# P-MT3620RDB-1-6_FTDI.net
KiCad netlist of a schematic drawn in Altium Designer
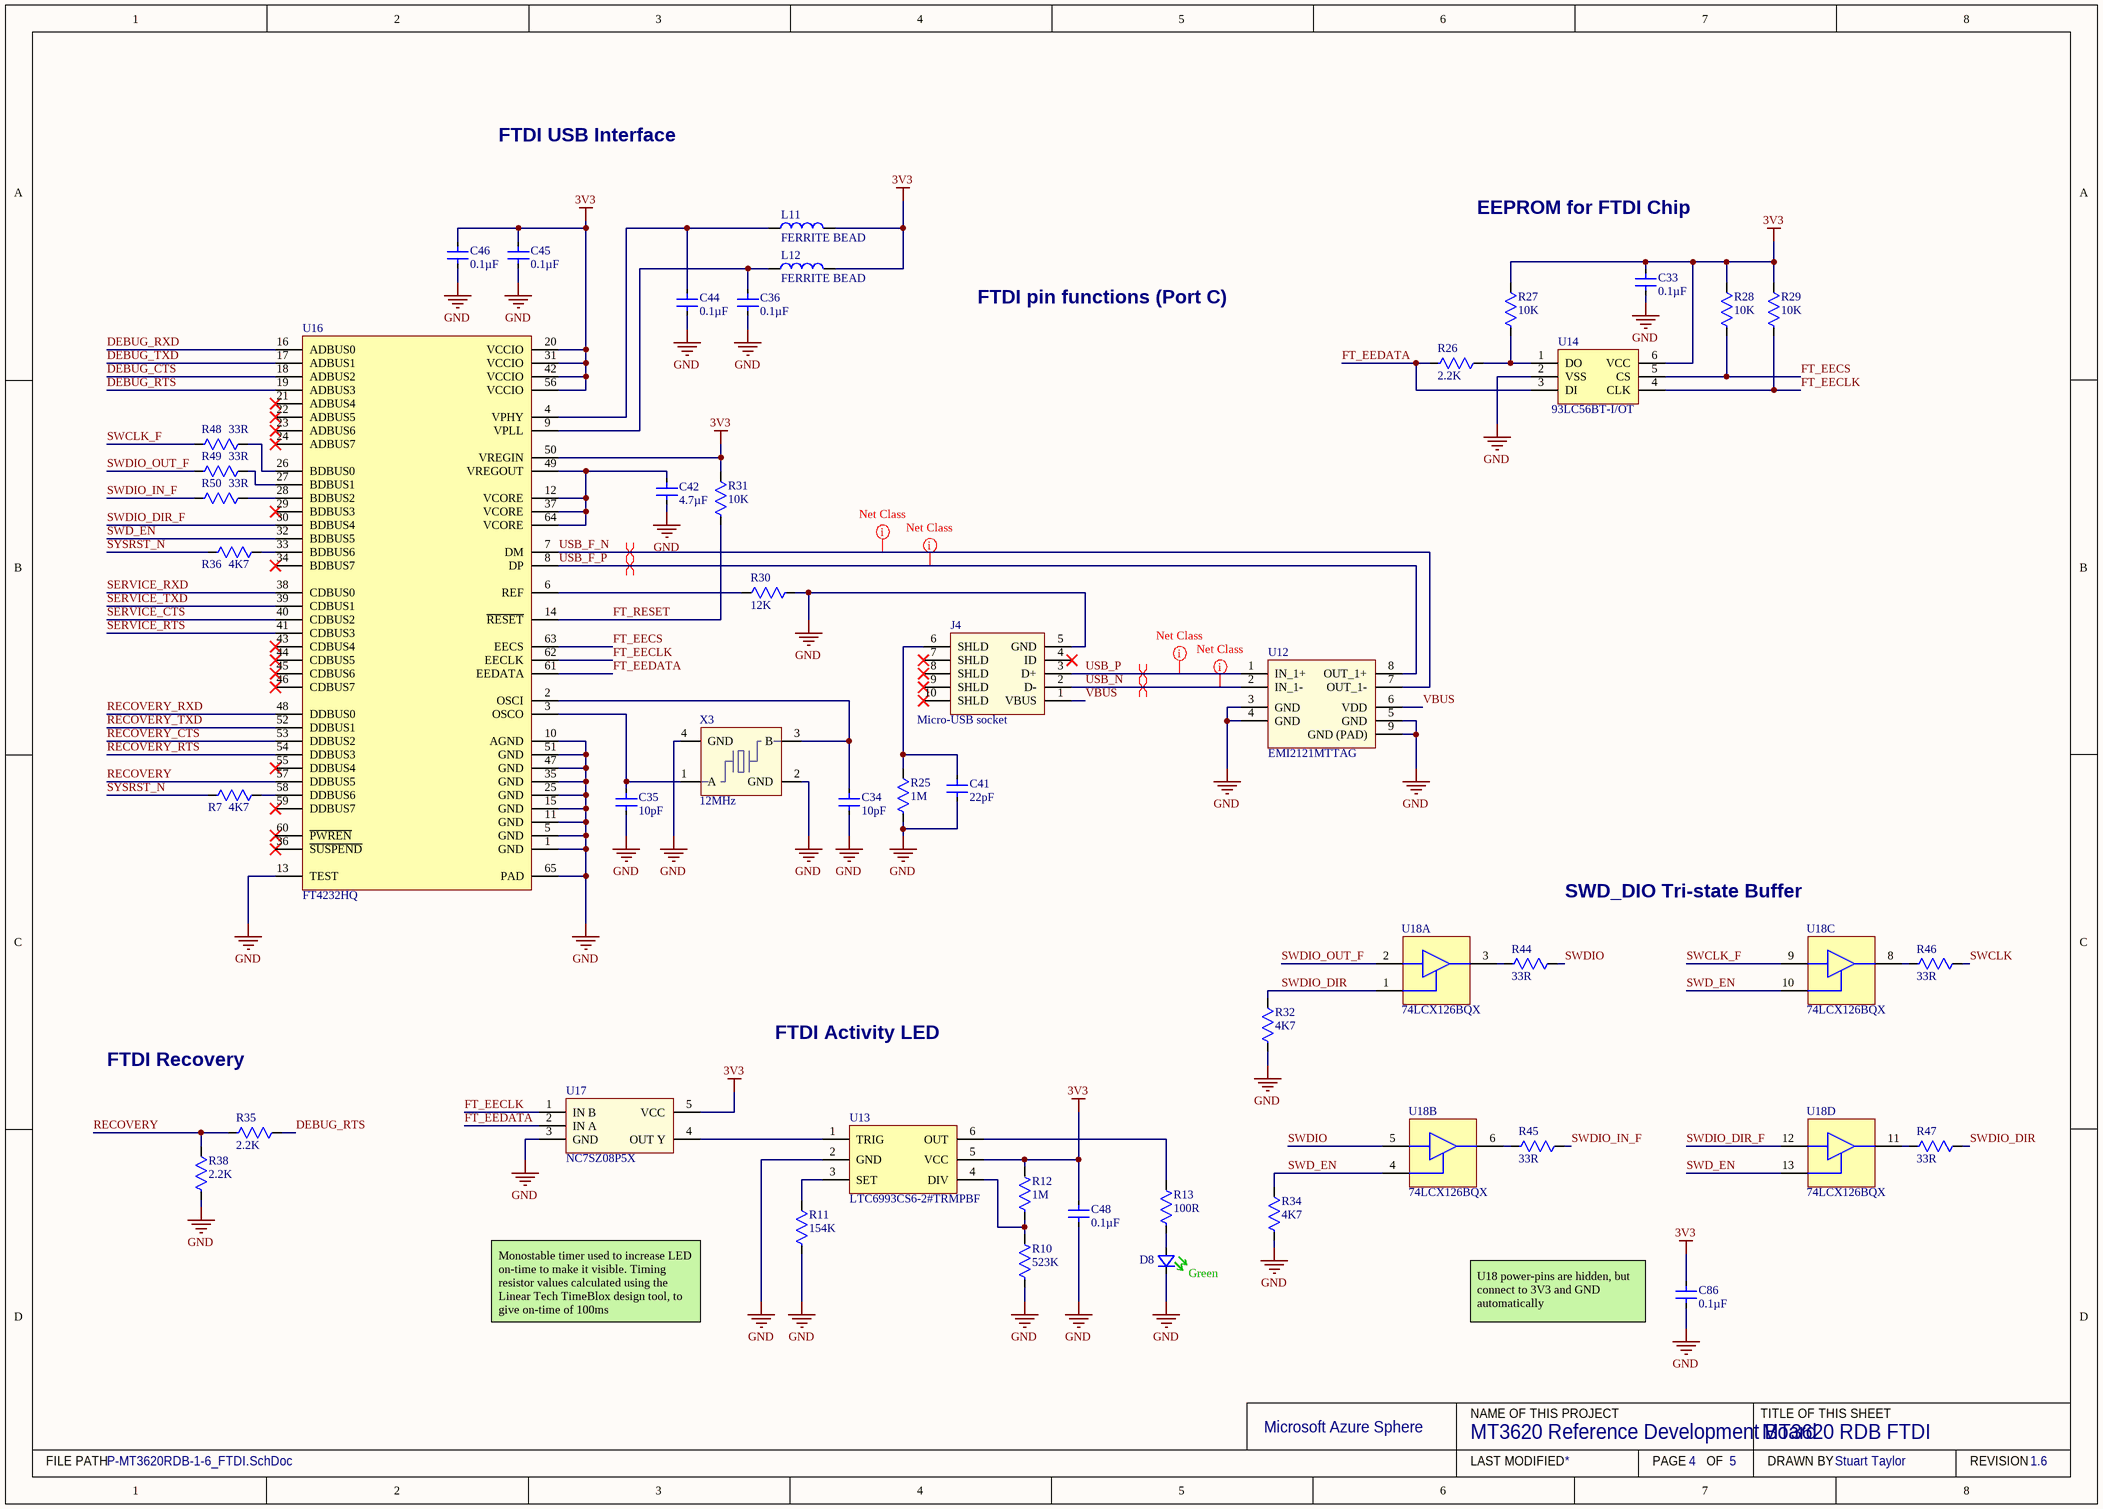
[diagram p0: P-MT3620RDB-1-6_FTDI.SchDoc]

(export (version "E")
  (design (tool "Eeschema 10.0.6"))
  (components
    (comp (ref "C33")
      (value "0.1µF")
      (footprint "CAPC1005-EIA0402 0.55MM MED")
      (description "CAP CER 0.1UF 50V 10% X7R 0402")
      (fields
        (field (name "MANUFACTURER") "TDK Corporation")
        (field (name "MANUFACTURER PART NUMBER") "C1005X7R1H104K050BB")
        (field (name "CAPACITANCE") "0.1µF")
      )
      (libsource (lib "TDK_Capacitor_C_0402") (part "0.1µF 0402 X7R 50V"))
    )
    (comp (ref "C34")
      (value "10pF")
      (footprint "CAPC1005-EIA0402 0.55MM MED")
      (description "CAP CER 10PF 50V NP0 0402")
      (fields
        (field (name "MANUFACTURER") "TDK Corporation")
        (field (name "MANUFACTURER PART NUMBER") "C1005C0G1H100D050BA")
        (field (name "CAPACITANCE") "10pF")
      )
      (libsource (lib "TDK_Capacitor_C_0402") (part "10pF 0402 C0G, NP0 50V"))
    )
    (comp (ref "C35")
      (value "10pF")
      (footprint "CAPC1005-EIA0402 0.55MM MED")
      (description "CAP CER 10PF 50V NP0 0402")
      (fields
        (field (name "MANUFACTURER") "TDK Corporation")
        (field (name "MANUFACTURER PART NUMBER") "C1005C0G1H100D050BA")
        (field (name "CAPACITANCE") "10pF")
      )
      (libsource (lib "TDK_Capacitor_C_0402") (part "10pF 0402 C0G, NP0 50V"))
    )
    (comp (ref "C36")
      (value "0.1µF")
      (footprint "CAPC1005-EIA0402 0.55MM MED")
      (description "CAP CER 0.1UF 50V 10% X7R 0402")
      (fields
        (field (name "MANUFACTURER") "TDK Corporation")
        (field (name "MANUFACTURER PART NUMBER") "C1005X7R1H104K050BB")
        (field (name "CAPACITANCE") "0.1µF")
      )
      (libsource (lib "TDK_Capacitor_C_0402") (part "0.1µF 0402 X7R 50V"))
    )
    (comp (ref "C41")
      (value "22pF")
      (footprint "CAPC1005-EIA0402 0.55MM MED")
      (description "CAP CER 22PF 50V 5% NP0 0402")
      (fields
        (field (name "MANUFACTURER") "TDK Corporation")
        (field (name "MANUFACTURER PART NUMBER") "C1005C0G1H220J050BA")
        (field (name "CAPACITANCE") "22pF")
      )
      (libsource (lib "TDK_Capacitor_C_0402") (part "22pF 0402 C0G, NP0 50V"))
    )
    (comp (ref "C42")
      (value "4.7µF")
      (footprint "CAPC1005-EIA0402 0.55MM MED")
      (description "CAP CER 4.7UF 10V 10% X5R 0402")
      (fields
        (field (name "MANUFACTURER") "TDK Corporation")
        (field (name "MANUFACTURER PART NUMBER") "C1005X5R1A475K050BC")
        (field (name "CAPACITANCE") "4.7µF")
      )
      (libsource (lib "TDK_Capacitor_C_0402") (part "4.7µF 0402 X5R 10V"))
    )
    (comp (ref "C44")
      (value "0.1µF")
      (footprint "CAPC1005-EIA0402 0.55MM MED")
      (description "CAP CER 0.1UF 50V 10% X7R 0402")
      (fields
        (field (name "MANUFACTURER") "TDK Corporation")
        (field (name "MANUFACTURER PART NUMBER") "C1005X7R1H104K050BB")
        (field (name "CAPACITANCE") "0.1µF")
      )
      (libsource (lib "TDK_Capacitor_C_0402") (part "0.1µF 0402 X7R 50V"))
    )
    (comp (ref "C45")
      (value "0.1µF")
      (footprint "CAPC1005-EIA0402 0.55MM MED")
      (description "CAP CER 0.1UF 50V 10% X7R 0402")
      (fields
        (field (name "MANUFACTURER") "TDK Corporation")
        (field (name "MANUFACTURER PART NUMBER") "C1005X7R1H104K050BB")
        (field (name "CAPACITANCE") "0.1µF")
      )
      (libsource (lib "TDK_Capacitor_C_0402") (part "0.1µF 0402 X7R 50V"))
    )
    (comp (ref "C46")
      (value "0.1µF")
      (footprint "CAPC1005-EIA0402 0.55MM MED")
      (description "CAP CER 0.1UF 50V 10% X7R 0402")
      (fields
        (field (name "MANUFACTURER") "TDK Corporation")
        (field (name "MANUFACTURER PART NUMBER") "C1005X7R1H104K050BB")
        (field (name "CAPACITANCE") "0.1µF")
      )
      (libsource (lib "TDK_Capacitor_C_0402") (part "0.1µF 0402 X7R 50V"))
    )
    (comp (ref "C48")
      (value "0.1µF")
      (footprint "CAPC1005-EIA0402 0.55MM MED")
      (description "CAP CER 0.1UF 50V 10% X7R 0402")
      (fields
        (field (name "MANUFACTURER") "TDK Corporation")
        (field (name "MANUFACTURER PART NUMBER") "C1005X7R1H104K050BB")
        (field (name "CAPACITANCE") "0.1µF")
      )
      (libsource (lib "TDK_Capacitor_C_0402") (part "0.1µF 0402 X7R 50V"))
    )
    (comp (ref "C86")
      (value "0.1µF")
      (footprint "CAPC1005-EIA0402 0.55MM MED")
      (description "CAP CER 0.1UF 50V 10% X7R 0402")
      (fields
        (field (name "MANUFACTURER") "TDK Corporation")
        (field (name "MANUFACTURER PART NUMBER") "C1005X7R1H104K050BB")
        (field (name "CAPACITANCE") "0.1µF")
      )
      (libsource (lib "TDK_Capacitor_C_0402") (part "0.1µF 0402 X7R 50V"))
    )
    (comp (ref "D8")
      (value "Green LED")
      (footprint "Rohm SML-D12 Green")
      (description "1.6 x 0.8 x 0.55mm (0603) LED 560nm Green")
      (fields
        (field (name "MANUFACTURER") "Rohm Semiconductor")
        (field (name "MANUFACTURER PART NUMBER") "SML-D12P8WT86")
        (field (name "COLOUR") "Green")
      )
      (libsource (lib "Rohm") (part "SML-D12P"))
    )
    (comp (ref "J4")
      (value "Micro-USB socket")
      (footprint "MCR-B-S-RA-SMT-CS5-T/R")
      (fields
        (field (name "MANUFACTURER") "Adam Tech")
        (field (name "MANUFACTURERS PART NUMBER") "MCR-B-S-RA-SMT-CS5-T/R")
      )
      (libsource (lib "AdamTech") (part "MCR-B-S-RA-SMT-CS5-T/R"))
    )
    (comp (ref "L11")
      (value "FERRITE BEAD")
      (footprint "CAPC1005-EIA0402 0.55MM MED")
      (description "FERRITE BEAD 120 OHM 0402 1LN")
      (fields
        (field (name "MANUFACTURER") "Murata Electronics North America")
        (field (name "MANUFACTURER PART NUMBER") "BLM15PD121SN1D")
      )
      (libsource (lib "Murata") (part "BLM15PD121SN1D"))
    )
    (comp (ref "L12")
      (value "FERRITE BEAD")
      (footprint "CAPC1005-EIA0402 0.55MM MED")
      (description "FERRITE BEAD 120 OHM 0402 1LN")
      (fields
        (field (name "MANUFACTURER") "Murata Electronics North America")
        (field (name "MANUFACTURER PART NUMBER") "BLM15PD121SN1D")
      )
      (libsource (lib "Murata") (part "BLM15PD121SN1D"))
    )
    (comp (ref "R7")
      (value "4K7")
      (footprint "RES 0402 MEDIUM DENSITY")
      (description "RES 4.7K OHM 1/10W 1% 0402 SMD")
      (fields
        (field (name "MANUFACTURER") "Panasonic Electronic Components")
        (field (name "MANUFACTURER PART NUMBER") "ERJ-2RKF4701X")
        (field (name "RESISTANCE (OHMS)") "4K7")
      )
      (libsource (lib "Panasonic_Resistor_ERJ2R") (part "4.7K"))
    )
    (comp (ref "R10")
      (value "523K")
      (footprint "RES 0402 MEDIUM DENSITY")
      (description "RES 523K OHM 1/10W 1% 0402 SMD")
      (fields
        (field (name "MANUFACTURER") "Panasonic Electronic Components")
        (field (name "MANUFACTURER PART NUMBER") "ERJ-2RKF5233X")
        (field (name "RESISTANCE (OHMS)") "523K")
      )
      (libsource (lib "Panasonic_Resistor_ERJ2R") (part "523K"))
    )
    (comp (ref "R11")
      (value "154K")
      (footprint "RES 0402 MEDIUM DENSITY")
      (description "RES 154K OHM 1/10W 1% 0402 SMD")
      (fields
        (field (name "MANUFACTURER") "Panasonic Electronic Components")
        (field (name "MANUFACTURER PART NUMBER") "ERJ-2RKF1543X")
        (field (name "RESISTANCE (OHMS)") "154K")
      )
      (libsource (lib "Panasonic_Resistor_ERJ2R") (part "154K"))
    )
    (comp (ref "R12")
      (value "1M")
      (footprint "RES 0402 MEDIUM DENSITY")
      (description "RES 1M OHM 1/10W 1% 0402 SMD")
      (fields
        (field (name "MANUFACTURER") "Panasonic Electronic Components")
        (field (name "MANUFACTURER PART NUMBER") "ERJ-2RKF1004X")
        (field (name "RESISTANCE (OHMS)") "1M")
      )
      (libsource (lib "Panasonic_Resistor_ERJ2R") (part "1M"))
    )
    (comp (ref "R13")
      (value "100R")
      (footprint "RES 0402 MEDIUM DENSITY")
      (description "RES 100 OHM 1/10W 1% 0402 SMD")
      (fields
        (field (name "MANUFACTURER") "Panasonic Electronic Components")
        (field (name "MANUFACTURER PART NUMBER") "ERJ-2RKF1000X")
        (field (name "RESISTANCE (OHMS)") "100R")
      )
      (libsource (lib "Panasonic_Resistor_ERJ2R") (part "100R"))
    )
    (comp (ref "R25")
      (value "1M")
      (footprint "RES 0402 MEDIUM DENSITY")
      (description "RES 1M OHM 1/10W 1% 0402 SMD")
      (fields
        (field (name "MANUFACTURER") "Panasonic Electronic Components")
        (field (name "MANUFACTURER PART NUMBER") "ERJ-2RKF1004X")
        (field (name "RESISTANCE (OHMS)") "1M")
      )
      (libsource (lib "Panasonic_Resistor_ERJ2R") (part "1M"))
    )
    (comp (ref "R26")
      (value "2.2K")
      (footprint "RES 0402 MEDIUM DENSITY")
      (description "RES 2.2K OHM 1/10W 1% 0402 SMD")
      (fields
        (field (name "MANUFACTURER") "Panasonic Electronic Components")
        (field (name "MANUFACTURER PART NUMBER") "ERJ-2RKF2201X")
        (field (name "RESISTANCE (OHMS)") "2.2K")
      )
      (libsource (lib "Panasonic_Resistor_ERJ2R") (part "2.2K"))
    )
    (comp (ref "R27")
      (value "10K")
      (footprint "RES 0402 MEDIUM DENSITY")
      (description "RES 10K OHM 1/10W 1% 0402 SMD")
      (fields
        (field (name "MANUFACTURER") "Panasonic Electronic Components")
        (field (name "MANUFACTURER PART NUMBER") "ERJ-2RKF1002X")
        (field (name "RESISTANCE (OHMS)") "10K")
      )
      (libsource (lib "Panasonic_Resistor_ERJ2R") (part "10K"))
    )
    (comp (ref "R28")
      (value "10K")
      (footprint "RES 0402 MEDIUM DENSITY")
      (description "RES 10K OHM 1/10W 1% 0402 SMD")
      (fields
        (field (name "MANUFACTURER") "Panasonic Electronic Components")
        (field (name "MANUFACTURER PART NUMBER") "ERJ-2RKF1002X")
        (field (name "RESISTANCE (OHMS)") "10K")
      )
      (libsource (lib "Panasonic_Resistor_ERJ2R") (part "10K"))
    )
    (comp (ref "R29")
      (value "10K")
      (footprint "RES 0402 MEDIUM DENSITY")
      (description "RES 10K OHM 1/10W 1% 0402 SMD")
      (fields
        (field (name "MANUFACTURER") "Panasonic Electronic Components")
        (field (name "MANUFACTURER PART NUMBER") "ERJ-2RKF1002X")
        (field (name "RESISTANCE (OHMS)") "10K")
      )
      (libsource (lib "Panasonic_Resistor_ERJ2R") (part "10K"))
    )
    (comp (ref "R30")
      (value "12K")
      (footprint "RES 0402 MEDIUM DENSITY")
      (description "RES 12K OHM 1/10W 1% 0402 SMD")
      (fields
        (field (name "MANUFACTURER") "Panasonic Electronic Components")
        (field (name "MANUFACTURER PART NUMBER") "ERJ-2RKF1202X")
        (field (name "RESISTANCE (OHMS)") "12K")
      )
      (libsource (lib "Panasonic_Resistor_ERJ2R") (part "12K"))
    )
    (comp (ref "R31")
      (value "10K")
      (footprint "RES 0402 MEDIUM DENSITY")
      (description "RES 10K OHM 1/10W 1% 0402 SMD")
      (fields
        (field (name "MANUFACTURER") "Panasonic Electronic Components")
        (field (name "MANUFACTURER PART NUMBER") "ERJ-2RKF1002X")
        (field (name "RESISTANCE (OHMS)") "10K")
      )
      (libsource (lib "Panasonic_Resistor_ERJ2R") (part "10K"))
    )
    (comp (ref "R32")
      (value "4K7")
      (footprint "RES 0402 MEDIUM DENSITY")
      (description "RES 4.7K OHM 1/10W 1% 0402 SMD")
      (fields
        (field (name "MANUFACTURER") "Panasonic Electronic Components")
        (field (name "MANUFACTURER PART NUMBER") "ERJ-2RKF4701X")
        (field (name "RESISTANCE (OHMS)") "4K7")
      )
      (libsource (lib "Panasonic_Resistor_ERJ2R") (part "4.7K"))
    )
    (comp (ref "R34")
      (value "4K7")
      (footprint "RES 0402 MEDIUM DENSITY")
      (description "RES 4.7K OHM 1/10W 1% 0402 SMD")
      (fields
        (field (name "MANUFACTURER") "Panasonic Electronic Components")
        (field (name "MANUFACTURER PART NUMBER") "ERJ-2RKF4701X")
        (field (name "RESISTANCE (OHMS)") "4K7")
      )
      (libsource (lib "Panasonic_Resistor_ERJ2R") (part "4.7K"))
    )
    (comp (ref "R35")
      (value "2.2K")
      (footprint "RES 0402 MEDIUM DENSITY")
      (description "RES 2.2K OHM 1/10W 1% 0402 SMD")
      (fields
        (field (name "MANUFACTURER") "Panasonic Electronic Components")
        (field (name "MANUFACTURER PART NUMBER") "ERJ-2RKF2201X")
        (field (name "RESISTANCE (OHMS)") "2.2K")
      )
      (libsource (lib "Panasonic_Resistor_ERJ2R") (part "2.2K"))
    )
    (comp (ref "R36")
      (value "4K7")
      (footprint "RES 0402 MEDIUM DENSITY")
      (description "RES 4.7K OHM 1/10W 1% 0402 SMD")
      (fields
        (field (name "MANUFACTURER") "Panasonic Electronic Components")
        (field (name "MANUFACTURER PART NUMBER") "ERJ-2RKF4701X")
        (field (name "RESISTANCE (OHMS)") "4K7")
      )
      (libsource (lib "Panasonic_Resistor_ERJ2R") (part "4.7K"))
    )
    (comp (ref "R38")
      (value "2.2K")
      (footprint "RES 0402 MEDIUM DENSITY")
      (description "RES 2.2K OHM 1/10W 1% 0402 SMD")
      (fields
        (field (name "MANUFACTURER") "Panasonic Electronic Components")
        (field (name "MANUFACTURER PART NUMBER") "ERJ-2RKF2201X")
        (field (name "RESISTANCE (OHMS)") "2.2K")
      )
      (libsource (lib "Panasonic_Resistor_ERJ2R") (part "2.2K"))
    )
    (comp (ref "R44")
      (value "33R")
      (footprint "RES 0402 MEDIUM DENSITY")
      (description "RES 33 OHM 1/10W 1% 0402 SMD")
      (fields
        (field (name "MANUFACTURER") "Panasonic Electronic Components")
        (field (name "MANUFACTURER PART NUMBER") "ERJ-2RKF33R0X")
        (field (name "RESISTANCE (OHMS)") "33R")
      )
      (libsource (lib "Panasonic_Resistor_ERJ2R") (part "33R"))
    )
    (comp (ref "R45")
      (value "33R")
      (footprint "RES 0402 MEDIUM DENSITY")
      (description "RES 33 OHM 1/10W 1% 0402 SMD")
      (fields
        (field (name "MANUFACTURER") "Panasonic Electronic Components")
        (field (name "MANUFACTURER PART NUMBER") "ERJ-2RKF33R0X")
        (field (name "RESISTANCE (OHMS)") "33R")
      )
      (libsource (lib "Panasonic_Resistor_ERJ2R") (part "33R"))
    )
    (comp (ref "R46")
      (value "33R")
      (footprint "RES 0402 MEDIUM DENSITY")
      (description "RES 33 OHM 1/10W 1% 0402 SMD")
      (fields
        (field (name "MANUFACTURER") "Panasonic Electronic Components")
        (field (name "MANUFACTURER PART NUMBER") "ERJ-2RKF33R0X")
        (field (name "RESISTANCE (OHMS)") "33R")
      )
      (libsource (lib "Panasonic_Resistor_ERJ2R") (part "33R"))
    )
    (comp (ref "R47")
      (value "33R")
      (footprint "RES 0402 MEDIUM DENSITY")
      (description "RES 33 OHM 1/10W 1% 0402 SMD")
      (fields
        (field (name "MANUFACTURER") "Panasonic Electronic Components")
        (field (name "MANUFACTURER PART NUMBER") "ERJ-2RKF33R0X")
        (field (name "RESISTANCE (OHMS)") "33R")
      )
      (libsource (lib "Panasonic_Resistor_ERJ2R") (part "33R"))
    )
    (comp (ref "R48")
      (value "33R")
      (footprint "RES 0402 MEDIUM DENSITY")
      (description "RES 33 OHM 1/10W 1% 0402 SMD")
      (fields
        (field (name "MANUFACTURER") "Panasonic Electronic Components")
        (field (name "MANUFACTURER PART NUMBER") "ERJ-2RKF33R0X")
        (field (name "RESISTANCE (OHMS)") "33R")
      )
      (libsource (lib "Panasonic_Resistor_ERJ2R") (part "33R"))
    )
    (comp (ref "R49")
      (value "33R")
      (footprint "RES 0402 MEDIUM DENSITY")
      (description "RES 33 OHM 1/10W 1% 0402 SMD")
      (fields
        (field (name "MANUFACTURER") "Panasonic Electronic Components")
        (field (name "MANUFACTURER PART NUMBER") "ERJ-2RKF33R0X")
        (field (name "RESISTANCE (OHMS)") "33R")
      )
      (libsource (lib "Panasonic_Resistor_ERJ2R") (part "33R"))
    )
    (comp (ref "R50")
      (value "33R")
      (footprint "RES 0402 MEDIUM DENSITY")
      (description "RES 33 OHM 1/10W 1% 0402 SMD")
      (fields
        (field (name "MANUFACTURER") "Panasonic Electronic Components")
        (field (name "MANUFACTURER PART NUMBER") "ERJ-2RKF33R0X")
        (field (name "RESISTANCE (OHMS)") "33R")
      )
      (libsource (lib "Panasonic_Resistor_ERJ2R") (part "33R"))
    )
    (comp (ref "U12")
      (value "EMI2121MTTAG")
      (footprint "EMI2121MTTAG")
      (description "IC FILTER COMMON MODE ESD 8WDFN")
      (fields (field (name "MANUFACTURER") "ON Semiconductor"))
      (libsource (lib "OnSemiconductor") (part "EMI2121MTTAG"))
    )
    (comp (ref "U13")
      (value "LTC6993CS6-2#TRMPBF")
      (footprint "LTC6993CS6-2#TRMPBF")
      (description "LINEAR TECHNOLOGY - LTC6993CS6-2#TRMPBF - GENERATOR, PULSE, TIMERBLOX, 6SOT-23")
      (fields (field (name "MANUFACTURER") "LINEAR TECHNOLOGY"))
      (libsource (lib "LinearTech") (part "LTC6993CS6-2#TRMPBF"))
    )
    (comp (ref "U14")
      (value "93LC56BT-I/OT")
      (footprint "SOT23-93C56B")
      (description "IC EEPROM 2KBIT 2MHZ SOT23-6")
      (fields (field (name "MANUFACTURER") "Microchip Technology"))
      (libsource (lib "Microchip") (part "93LC56BT-I/OT"))
    )
    (comp (ref "U16")
      (value "FT4232HQ")
      (footprint "FTDI_TF4232HQ_64QFN")
      (description "IC USB HS QUAD UART/SYNC 64-QFN")
      (fields
        (field (name "MANUFACTURER") "FTDI, Future Technology Devices International Ltd")
        (field (name "MANUFACTURER PART NUMBER") "FT4232HQ-REEL")
      )
      (libsource (lib "FTDI") (part "FT4232HQ"))
    )
    (comp (ref "U17")
      (value "NC7SZ08P5X")
      (footprint "SC-70-5")
      (description "IC GATE AND 1CH 2-INP SC-70-5")
      (fields (field (name "MANUFACTURER") "Fairchild Semiconductor"))
      (libsource (lib "OnSemiconductor") (part "NC7SZ08P5X"))
    )
    (comp (ref "U18")
      (value "74LCX126BQX")
      (footprint "74LCX126BQX")
      (description "IC BUFFER QUAD LV N-INV 14DQFN")
      (fields (field (name "MANUFACTURER") "Fairchild Semiconductor"))
      (libsource (lib "OnSemiconductor") (part "74LCX126BQX"))
    )
    (comp (ref "X3")
      (value "12MHz")
      (footprint "TXC 8Z")
      (description "CRYSTAL 12.000 MHZ 18PF SMD")
      (fields
        (field (name "MANUFACTURER") "TXC CORPORATION")
        (field (name "MANUFACTURER PART NUMBER") "8Z-12.000MAAJ-T")
        (field (name "FREQUENCY") "12MHz")
      )
      (libsource (lib "crystal") (part "CRYSTAL 12MHz 18pF SMD"))
    )
  )
  (nets
    (net (code "1") (name "/DEBUG_CTS") (class "Default")
      (node (ref "U16") (pin "18") (pinfunction "ADBUS2_18") (pintype "passive"))
    )
    (net (code "2") (name "/DEBUG_RTS") (class "Default")
      (node (ref "R35") (pin "1") (pinfunction "1_1") (pintype "passive"))
      (node (ref "U16") (pin "19") (pinfunction "ADBUS3_19") (pintype "passive"))
    )
    (net (code "3") (name "/DEBUG_RXD") (class "Default")
      (node (ref "U16") (pin "16") (pinfunction "ADBUS0_16") (pintype "passive"))
    )
    (net (code "4") (name "/DEBUG_TXD") (class "Default")
      (node (ref "U16") (pin "17") (pinfunction "ADBUS1_17") (pintype "passive"))
    )
    (net (code "5") (name "/FT_EECLK") (class "Default")
      (node (ref "R29") (pin "2") (pinfunction "2_2") (pintype "passive"))
      (node (ref "U14") (pin "4") (pinfunction "CLK_4") (pintype "passive"))
      (node (ref "U16") (pin "62") (pinfunction "EECLK_62") (pintype "passive"))
      (node (ref "U17") (pin "1") (pinfunction "IN_B_1") (pintype "passive"))
    )
    (net (code "6") (name "/FT_EECS") (class "Default")
      (node (ref "R28") (pin "2") (pinfunction "2_2") (pintype "passive"))
      (node (ref "U14") (pin "5") (pinfunction "CS_5") (pintype "passive"))
      (node (ref "U16") (pin "63") (pinfunction "EECS_63") (pintype "passive"))
    )
    (net (code "7") (name "/FT_EEDATA") (class "Default")
      (node (ref "R26") (pin "2") (pinfunction "2_2") (pintype "passive"))
      (node (ref "U14") (pin "3") (pinfunction "DI_3") (pintype "passive"))
      (node (ref "U16") (pin "61") (pinfunction "EEDATA_61") (pintype "passive"))
      (node (ref "U17") (pin "2") (pinfunction "IN_A_2") (pintype "passive"))
    )
    (net (code "8") (name "/FT_RESET") (class "Default")
      (node (ref "R31") (pin "2") (pinfunction "2_2") (pintype "passive"))
      (node (ref "U16") (pin "14") (pinfunction "~{RESET}_14") (pintype "passive"))
    )
    (net (code "9") (name "/RECOVERY") (class "Default")
      (node (ref "R35") (pin "2") (pinfunction "2_2") (pintype "passive"))
      (node (ref "R38") (pin "1") (pinfunction "1_1") (pintype "passive"))
      (node (ref "U16") (pin "57") (pinfunction "DDBUS5_57") (pintype "passive"))
    )
    (net (code "10") (name "/RECOVERY_CTS") (class "Default")
      (node (ref "U16") (pin "53") (pinfunction "DDBUS2_53") (pintype "passive"))
    )
    (net (code "11") (name "/RECOVERY_RTS") (class "Default")
      (node (ref "U16") (pin "54") (pinfunction "DDBUS3_54") (pintype "passive"))
    )
    (net (code "12") (name "/RECOVERY_RXD") (class "Default")
      (node (ref "U16") (pin "48") (pinfunction "DDBUS0_48") (pintype "passive"))
    )
    (net (code "13") (name "/RECOVERY_TXD") (class "Default")
      (node (ref "U16") (pin "52") (pinfunction "DDBUS1_52") (pintype "passive"))
    )
    (net (code "14") (name "/SERVICE_CTS") (class "Default")
      (node (ref "U16") (pin "40") (pinfunction "CDBUS2_40") (pintype "passive"))
    )
    (net (code "15") (name "/SERVICE_RTS") (class "Default")
      (node (ref "U16") (pin "41") (pinfunction "CDBUS3_41") (pintype "passive"))
    )
    (net (code "16") (name "/SERVICE_RXD") (class "Default")
      (node (ref "U16") (pin "38") (pinfunction "CDBUS0_38") (pintype "passive"))
    )
    (net (code "17") (name "/SERVICE_TXD") (class "Default")
      (node (ref "U16") (pin "39") (pinfunction "CDBUS1_39") (pintype "passive"))
    )
    (net (code "18") (name "/SWCLK") (class "Default")
      (node (ref "R46") (pin "1") (pinfunction "1_1") (pintype "passive"))
    )
    (net (code "19") (name "/SWCLK_F") (class "Default")
      (node (ref "R48") (pin "2") (pinfunction "2_2") (pintype "passive"))
      (node (ref "U18") (pin "9") (pinfunction "3A_9") (pintype "passive"))
    )
    (net (code "20") (name "/SWDIO") (class "Default")
      (node (ref "R44") (pin "1") (pinfunction "1_1") (pintype "passive"))
      (node (ref "U18") (pin "5") (pinfunction "2A_5") (pintype "passive"))
    )
    (net (code "21") (name "/SWDIO_DIR") (class "Default")
      (node (ref "R32") (pin "1") (pinfunction "1_1") (pintype "passive"))
      (node (ref "R47") (pin "1") (pinfunction "1_1") (pintype "passive"))
      (node (ref "U18") (pin "1") (pinfunction "1OE_1") (pintype "passive"))
    )
    (net (code "22") (name "/SWDIO_DIR_F") (class "Default")
      (node (ref "U16") (pin "30") (pinfunction "BDBUS4_30") (pintype "passive"))
      (node (ref "U18") (pin "12") (pinfunction "4A_12") (pintype "passive"))
    )
    (net (code "23") (name "/SWDIO_IN_F") (class "Default")
      (node (ref "R45") (pin "1") (pinfunction "1_1") (pintype "passive"))
      (node (ref "R50") (pin "2") (pinfunction "2_2") (pintype "passive"))
    )
    (net (code "24") (name "/SWDIO_OUT_F") (class "Default")
      (node (ref "R49") (pin "2") (pinfunction "2_2") (pintype "passive"))
      (node (ref "U18") (pin "2") (pinfunction "1A_2") (pintype "passive"))
    )
    (net (code "25") (name "/SWD_EN") (class "Default")
      (node (ref "R34") (pin "1") (pinfunction "1_1") (pintype "passive"))
      (node (ref "U16") (pin "32") (pinfunction "BDBUS5_32") (pintype "passive"))
      (node (ref "U18") (pin "10") (pinfunction "3OE_10") (pintype "passive"))
      (node (ref "U18") (pin "13") (pinfunction "4OE_13") (pintype "passive"))
      (node (ref "U18") (pin "4") (pinfunction "2OE_4") (pintype "passive"))
    )
    (net (code "26") (name "/SYSRST_N") (class "Default")
      (node (ref "R36") (pin "2") (pinfunction "2_2") (pintype "passive"))
      (node (ref "R7") (pin "2") (pinfunction "2_2") (pintype "passive"))
    )
    (net (code "27") (name "/USB_F_N") (class "Default")
      (node (ref "U12") (pin "7") (pinfunction "OUT_1-_7") (pintype "passive"))
      (node (ref "U16") (pin "7") (pinfunction "DM_7") (pintype "passive"))
    )
    (net (code "28") (name "/USB_F_P") (class "Default")
      (node (ref "U12") (pin "8") (pinfunction "OUT_1+_8") (pintype "passive"))
      (node (ref "U16") (pin "8") (pinfunction "DP_8") (pintype "passive"))
    )
    (net (code "29") (name "/USB_N") (class "Default")
      (node (ref "J4") (pin "2") (pinfunction "D-_2") (pintype "passive"))
      (node (ref "U12") (pin "2") (pinfunction "IN_1-_2") (pintype "passive"))
    )
    (net (code "30") (name "/USB_P") (class "Default")
      (node (ref "J4") (pin "3") (pinfunction "D+_3") (pintype "passive"))
      (node (ref "U12") (pin "1") (pinfunction "IN_1+_1") (pintype "passive"))
    )
    (net (code "31") (name "/VBUS") (class "Default")
      (node (ref "J4") (pin "1") (pinfunction "VBUS_1") (pintype "passive"))
      (node (ref "U12") (pin "6") (pinfunction "VDD_6") (pintype "passive"))
    )
    (net (code "32") (name "3V3") (class "Default")
      (node (ref "C33") (pin "2") (pinfunction "2_2") (pintype "passive"))
      (node (ref "C45") (pin "2") (pinfunction "2_2") (pintype "passive"))
      (node (ref "C46") (pin "2") (pinfunction "2_2") (pintype "passive"))
      (node (ref "C48") (pin "2") (pinfunction "2_2") (pintype "passive"))
      (node (ref "C86") (pin "2") (pinfunction "2_2") (pintype "passive"))
      (node (ref "L11") (pin "2") (pinfunction "2_2") (pintype "passive"))
      (node (ref "L12") (pin "2") (pinfunction "2_2") (pintype "passive"))
      (node (ref "R12") (pin "1") (pinfunction "1_1") (pintype "passive"))
      (node (ref "R27") (pin "1") (pinfunction "1_1") (pintype "passive"))
      (node (ref "R28") (pin "1") (pinfunction "1_1") (pintype "passive"))
      (node (ref "R29") (pin "1") (pinfunction "1_1") (pintype "passive"))
      (node (ref "R31") (pin "1") (pinfunction "1_1") (pintype "passive"))
      (node (ref "U13") (pin "5") (pinfunction "VCC_5") (pintype "passive"))
      (node (ref "U14") (pin "6") (pinfunction "VCC_6") (pintype "passive"))
      (node (ref "U16") (pin "20") (pinfunction "VCCIO_20") (pintype "passive"))
      (node (ref "U16") (pin "31") (pinfunction "VCCIO_31") (pintype "passive"))
      (node (ref "U16") (pin "42") (pinfunction "VCCIO_42") (pintype "passive"))
      (node (ref "U16") (pin "50") (pinfunction "VREGIN_50") (pintype "passive"))
      (node (ref "U16") (pin "56") (pinfunction "VCCIO_56") (pintype "passive"))
      (node (ref "U17") (pin "5") (pinfunction "VCC_5") (pintype "passive"))
      (node (ref "U18") (pin "14") (pinfunction "3V3_14") (pintype "power_in"))
    )
    (net (code "33") (name "GND") (class "Default")
      (node (ref "C33") (pin "1") (pinfunction "1_1") (pintype "passive"))
      (node (ref "C34") (pin "1") (pinfunction "1_1") (pintype "passive"))
      (node (ref "C35") (pin "1") (pinfunction "1_1") (pintype "passive"))
      (node (ref "C36") (pin "1") (pinfunction "1_1") (pintype "passive"))
      (node (ref "C41") (pin "1") (pinfunction "1_1") (pintype "passive"))
      (node (ref "C42") (pin "1") (pinfunction "1_1") (pintype "passive"))
      (node (ref "C44") (pin "1") (pinfunction "1_1") (pintype "passive"))
      (node (ref "C45") (pin "1") (pinfunction "1_1") (pintype "passive"))
      (node (ref "C46") (pin "1") (pinfunction "1_1") (pintype "passive"))
      (node (ref "C48") (pin "1") (pinfunction "1_1") (pintype "passive"))
      (node (ref "C86") (pin "1") (pinfunction "1_1") (pintype "passive"))
      (node (ref "D8") (pin "1") (pinfunction "K_1") (pintype "passive"))
      (node (ref "J4") (pin "5") (pinfunction "GND_5") (pintype "passive"))
      (node (ref "R10") (pin "2") (pinfunction "2_2") (pintype "passive"))
      (node (ref "R11") (pin "2") (pinfunction "2_2") (pintype "passive"))
      (node (ref "R25") (pin "2") (pinfunction "2_2") (pintype "passive"))
      (node (ref "R30") (pin "2") (pinfunction "2_2") (pintype "passive"))
      (node (ref "R32") (pin "2") (pinfunction "2_2") (pintype "passive"))
      (node (ref "R34") (pin "2") (pinfunction "2_2") (pintype "passive"))
      (node (ref "R38") (pin "2") (pinfunction "2_2") (pintype "passive"))
      (node (ref "U12") (pin "3") (pinfunction "GND_3") (pintype "passive"))
      (node (ref "U12") (pin "4") (pinfunction "GND_4") (pintype "passive"))
      (node (ref "U12") (pin "5") (pinfunction "GND_5") (pintype "passive"))
      (node (ref "U12") (pin "9") (pinfunction "GND_(PAD)_9") (pintype "passive"))
      (node (ref "U13") (pin "2") (pinfunction "GND_2") (pintype "passive"))
      (node (ref "U14") (pin "2") (pinfunction "VSS_2") (pintype "passive"))
      (node (ref "U16") (pin "1") (pinfunction "GND_1") (pintype "passive"))
      (node (ref "U16") (pin "10") (pinfunction "AGND_10") (pintype "passive"))
      (node (ref "U16") (pin "11") (pinfunction "GND_11") (pintype "passive"))
      (node (ref "U16") (pin "13") (pinfunction "TEST_13") (pintype "passive"))
      (node (ref "U16") (pin "15") (pinfunction "GND_15") (pintype "passive"))
      (node (ref "U16") (pin "25") (pinfunction "GND_25") (pintype "passive"))
      (node (ref "U16") (pin "35") (pinfunction "GND_35") (pintype "passive"))
      (node (ref "U16") (pin "47") (pinfunction "GND_47") (pintype "passive"))
      (node (ref "U16") (pin "5") (pinfunction "GND_5") (pintype "passive"))
      (node (ref "U16") (pin "51") (pinfunction "GND_51") (pintype "passive"))
      (node (ref "U16") (pin "65") (pinfunction "PAD_65") (pintype "passive"))
      (node (ref "U17") (pin "3") (pinfunction "GND_3") (pintype "passive"))
      (node (ref "U18") (pin "7") (pinfunction "GND_7") (pintype "power_in"))
      (node (ref "X3") (pin "2") (pinfunction "GND_2") (pintype "passive"))
      (node (ref "X3") (pin "4") (pinfunction "GND_4") (pintype "passive"))
    )
    (net (code "34") (name "Net-(C41-Pad2)") (class "Default")
      (node (ref "C41") (pin "2") (pinfunction "2_2") (pintype "passive"))
      (node (ref "J4") (pin "6") (pinfunction "SHLD_6") (pintype "passive"))
      (node (ref "R25") (pin "1") (pinfunction "1_1") (pintype "passive"))
    )
    (net (code "35") (name "Net-(D8-A)") (class "Default")
      (node (ref "D8") (pin "2") (pinfunction "A_2") (pintype "passive"))
      (node (ref "R13") (pin "2") (pinfunction "2_2") (pintype "passive"))
    )
    (net (code "36") (name "Net-(U13-DIV)") (class "Default")
      (node (ref "R10") (pin "1") (pinfunction "1_1") (pintype "passive"))
      (node (ref "R12") (pin "2") (pinfunction "2_2") (pintype "passive"))
      (node (ref "U13") (pin "4") (pinfunction "DIV_4") (pintype "passive"))
    )
    (net (code "37") (name "Net-(U13-OUT)") (class "Default")
      (node (ref "R13") (pin "1") (pinfunction "1_1") (pintype "passive"))
      (node (ref "U13") (pin "6") (pinfunction "OUT_6") (pintype "passive"))
    )
    (net (code "38") (name "Net-(U13-SET)") (class "Default")
      (node (ref "R11") (pin "1") (pinfunction "1_1") (pintype "passive"))
      (node (ref "U13") (pin "3") (pinfunction "SET_3") (pintype "passive"))
    )
    (net (code "39") (name "Net-(U13-TRIG)") (class "Default")
      (node (ref "U13") (pin "1") (pinfunction "TRIG_1") (pintype "passive"))
      (node (ref "U17") (pin "4") (pinfunction "OUT_Y_4") (pintype "passive"))
    )
    (net (code "40") (name "Net-(U14-DO)") (class "Default")
      (node (ref "R26") (pin "1") (pinfunction "1_1") (pintype "passive"))
      (node (ref "R27") (pin "2") (pinfunction "2_2") (pintype "passive"))
      (node (ref "U14") (pin "1") (pinfunction "DO_1") (pintype "passive"))
    )
    (net (code "41") (name "Net-(U16-BDBUS0)") (class "Default")
      (node (ref "R48") (pin "1") (pinfunction "1_1") (pintype "passive"))
      (node (ref "U16") (pin "26") (pinfunction "BDBUS0_26") (pintype "passive"))
    )
    (net (code "42") (name "Net-(U16-BDBUS1)") (class "Default")
      (node (ref "R49") (pin "1") (pinfunction "1_1") (pintype "passive"))
      (node (ref "U16") (pin "27") (pinfunction "BDBUS1_27") (pintype "passive"))
    )
    (net (code "43") (name "Net-(U16-BDBUS2)") (class "Default")
      (node (ref "R50") (pin "1") (pinfunction "1_1") (pintype "passive"))
      (node (ref "U16") (pin "28") (pinfunction "BDBUS2_28") (pintype "passive"))
    )
    (net (code "44") (name "Net-(U16-BDBUS6)") (class "Default")
      (node (ref "R36") (pin "1") (pinfunction "1_1") (pintype "passive"))
      (node (ref "U16") (pin "33") (pinfunction "BDBUS6_33") (pintype "passive"))
    )
    (net (code "45") (name "Net-(U16-DDBUS6)") (class "Default")
      (node (ref "R7") (pin "1") (pinfunction "1_1") (pintype "passive"))
      (node (ref "U16") (pin "58") (pinfunction "DDBUS6_58") (pintype "passive"))
    )
    (net (code "46") (name "Net-(U16-OSCI)") (class "Default")
      (node (ref "C34") (pin "2") (pinfunction "2_2") (pintype "passive"))
      (node (ref "U16") (pin "2") (pinfunction "OSCI_2") (pintype "passive"))
      (node (ref "X3") (pin "3") (pinfunction "B_3") (pintype "passive"))
    )
    (net (code "47") (name "Net-(U16-OSCO)") (class "Default")
      (node (ref "C35") (pin "2") (pinfunction "2_2") (pintype "passive"))
      (node (ref "U16") (pin "3") (pinfunction "OSCO_3") (pintype "passive"))
      (node (ref "X3") (pin "1") (pinfunction "A_1") (pintype "passive"))
    )
    (net (code "48") (name "Net-(U16-REF)") (class "Default")
      (node (ref "R30") (pin "1") (pinfunction "1_1") (pintype "passive"))
      (node (ref "U16") (pin "6") (pinfunction "REF_6") (pintype "passive"))
    )
    (net (code "49") (name "Net-(U16-VPHY)") (class "Default")
      (node (ref "C44") (pin "2") (pinfunction "2_2") (pintype "passive"))
      (node (ref "L11") (pin "1") (pinfunction "1_1") (pintype "passive"))
      (node (ref "U16") (pin "4") (pinfunction "VPHY_4") (pintype "passive"))
    )
    (net (code "50") (name "Net-(U16-VPLL)") (class "Default")
      (node (ref "C36") (pin "2") (pinfunction "2_2") (pintype "passive"))
      (node (ref "L12") (pin "1") (pinfunction "1_1") (pintype "passive"))
      (node (ref "U16") (pin "9") (pinfunction "VPLL_9") (pintype "passive"))
    )
    (net (code "51") (name "Net-(U16-VREGOUT)") (class "Default")
      (node (ref "C42") (pin "2") (pinfunction "2_2") (pintype "passive"))
      (node (ref "U16") (pin "12") (pinfunction "VCORE_12") (pintype "passive"))
      (node (ref "U16") (pin "37") (pinfunction "VCORE_37") (pintype "passive"))
      (node (ref "U16") (pin "49") (pinfunction "VREGOUT_49") (pintype "passive"))
      (node (ref "U16") (pin "64") (pinfunction "VCORE_64") (pintype "passive"))
    )
    (net (code "52") (name "Net-(U18A-1Y)") (class "Default")
      (node (ref "R44") (pin "2") (pinfunction "2_2") (pintype "passive"))
      (node (ref "U18") (pin "3") (pinfunction "1Y_3") (pintype "passive"))
    )
    (net (code "53") (name "Net-(U18B-2Y)") (class "Default")
      (node (ref "R45") (pin "2") (pinfunction "2_2") (pintype "passive"))
      (node (ref "U18") (pin "6") (pinfunction "2Y_6") (pintype "passive"))
    )
    (net (code "54") (name "Net-(U18C-3Y)") (class "Default")
      (node (ref "R46") (pin "2") (pinfunction "2_2") (pintype "passive"))
      (node (ref "U18") (pin "8") (pinfunction "3Y_8") (pintype "passive"))
    )
    (net (code "55") (name "Net-(U18D-4Y)") (class "Default")
      (node (ref "R47") (pin "2") (pinfunction "2_2") (pintype "passive"))
      (node (ref "U18") (pin "11") (pinfunction "4Y_11") (pintype "passive"))
    )
    (net (code "56") (name "unconnected-(J4-ID-Pad4)") (class "Default")
      (node (ref "J4") (pin "4") (pinfunction "ID_4") (pintype "passive+no_connect"))
    )
    (net (code "57") (name "unconnected-(J4-SHLD-Pad7)") (class "Default")
      (node (ref "J4") (pin "7") (pinfunction "SHLD_7") (pintype "passive+no_connect"))
    )
    (net (code "58") (name "unconnected-(J4-SHLD-Pad8)") (class "Default")
      (node (ref "J4") (pin "8") (pinfunction "SHLD_8") (pintype "passive+no_connect"))
    )
    (net (code "59") (name "unconnected-(J4-SHLD-Pad9)") (class "Default")
      (node (ref "J4") (pin "9") (pinfunction "SHLD_9") (pintype "passive+no_connect"))
    )
    (net (code "60") (name "unconnected-(J4-SHLD-Pad10)") (class "Default")
      (node (ref "J4") (pin "10") (pinfunction "SHLD_10") (pintype "passive+no_connect"))
    )
    (net (code "61") (name "unconnected-(U16-ADBUS4-Pad21)") (class "Default")
      (node (ref "U16") (pin "21") (pinfunction "ADBUS4_21") (pintype "passive+no_connect"))
    )
    (net (code "62") (name "unconnected-(U16-ADBUS5-Pad22)") (class "Default")
      (node (ref "U16") (pin "22") (pinfunction "ADBUS5_22") (pintype "passive+no_connect"))
    )
    (net (code "63") (name "unconnected-(U16-ADBUS6-Pad23)") (class "Default")
      (node (ref "U16") (pin "23") (pinfunction "ADBUS6_23") (pintype "passive+no_connect"))
    )
    (net (code "64") (name "unconnected-(U16-ADBUS7-Pad24)") (class "Default")
      (node (ref "U16") (pin "24") (pinfunction "ADBUS7_24") (pintype "passive+no_connect"))
    )
    (net (code "65") (name "unconnected-(U16-BDBUS3-Pad29)") (class "Default")
      (node (ref "U16") (pin "29") (pinfunction "BDBUS3_29") (pintype "passive+no_connect"))
    )
    (net (code "66") (name "unconnected-(U16-BDBUS7-Pad34)") (class "Default")
      (node (ref "U16") (pin "34") (pinfunction "BDBUS7_34") (pintype "passive+no_connect"))
    )
    (net (code "67") (name "unconnected-(U16-CDBUS4-Pad43)") (class "Default")
      (node (ref "U16") (pin "43") (pinfunction "CDBUS4_43") (pintype "passive+no_connect"))
    )
    (net (code "68") (name "unconnected-(U16-CDBUS5-Pad44)") (class "Default")
      (node (ref "U16") (pin "44") (pinfunction "CDBUS5_44") (pintype "passive+no_connect"))
    )
    (net (code "69") (name "unconnected-(U16-CDBUS6-Pad45)") (class "Default")
      (node (ref "U16") (pin "45") (pinfunction "CDBUS6_45") (pintype "passive+no_connect"))
    )
    (net (code "70") (name "unconnected-(U16-CDBUS7-Pad46)") (class "Default")
      (node (ref "U16") (pin "46") (pinfunction "CDBUS7_46") (pintype "passive+no_connect"))
    )
    (net (code "71") (name "unconnected-(U16-DDBUS4-Pad55)") (class "Default")
      (node (ref "U16") (pin "55") (pinfunction "DDBUS4_55") (pintype "passive+no_connect"))
    )
    (net (code "72") (name "unconnected-(U16-DDBUS7-Pad59)") (class "Default")
      (node (ref "U16") (pin "59") (pinfunction "DDBUS7_59") (pintype "passive+no_connect"))
    )
    (net (code "73") (name "unconnected-(U16-~{PWREN}-Pad60)") (class "Default")
      (node (ref "U16") (pin "60") (pinfunction "~{PWREN}_60") (pintype "passive+no_connect"))
    )
    (net (code "74") (name "unconnected-(U16-~{SUSPEND}-Pad36)") (class "Default")
      (node (ref "U16") (pin "36") (pinfunction "~{SUSPEND}_36") (pintype "passive+no_connect"))
    )
  )
)
